# development_board.net
KiCad netlist of a schematic drawn in EAGLE
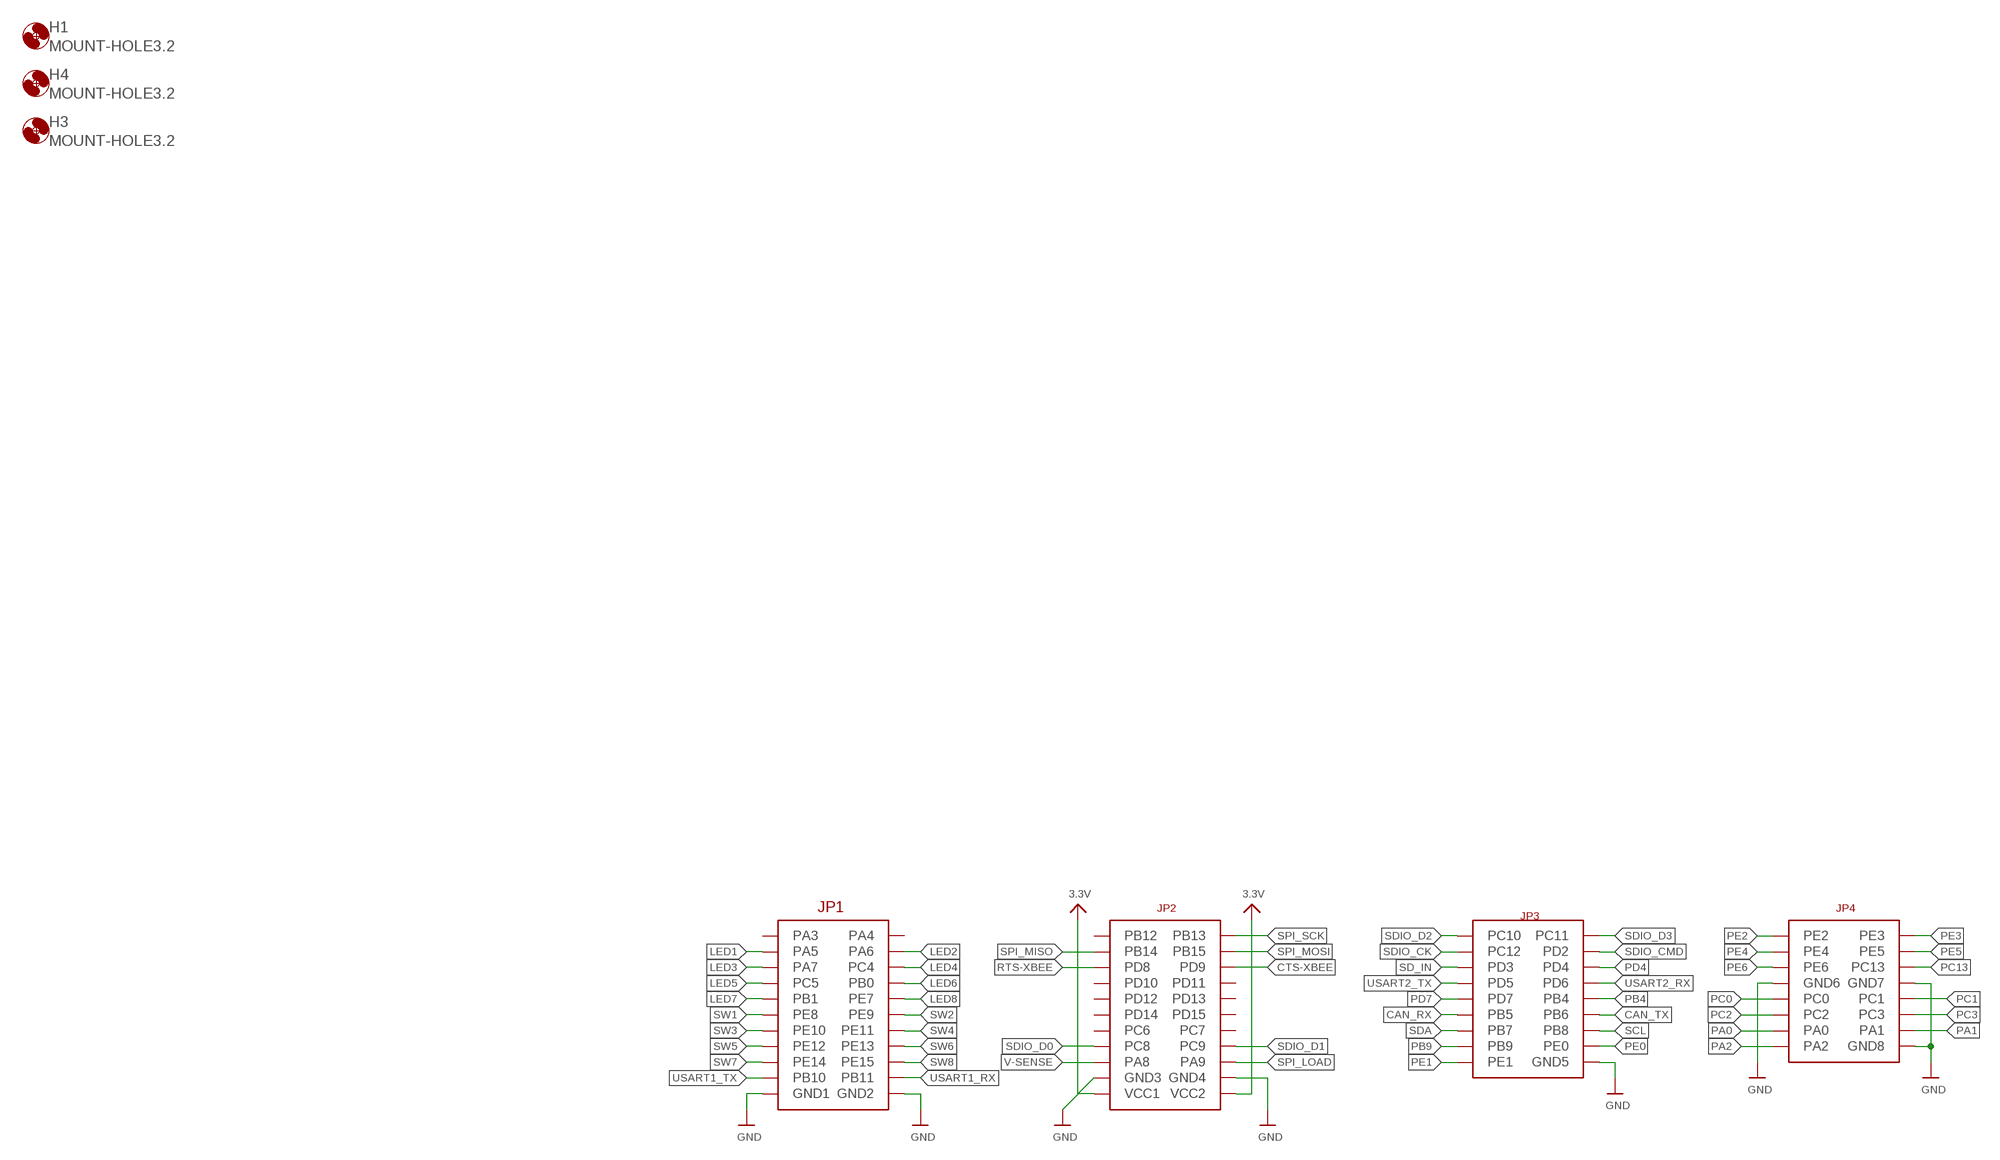
[diagram p0: schematic, sheet 1, part 1 of 3]
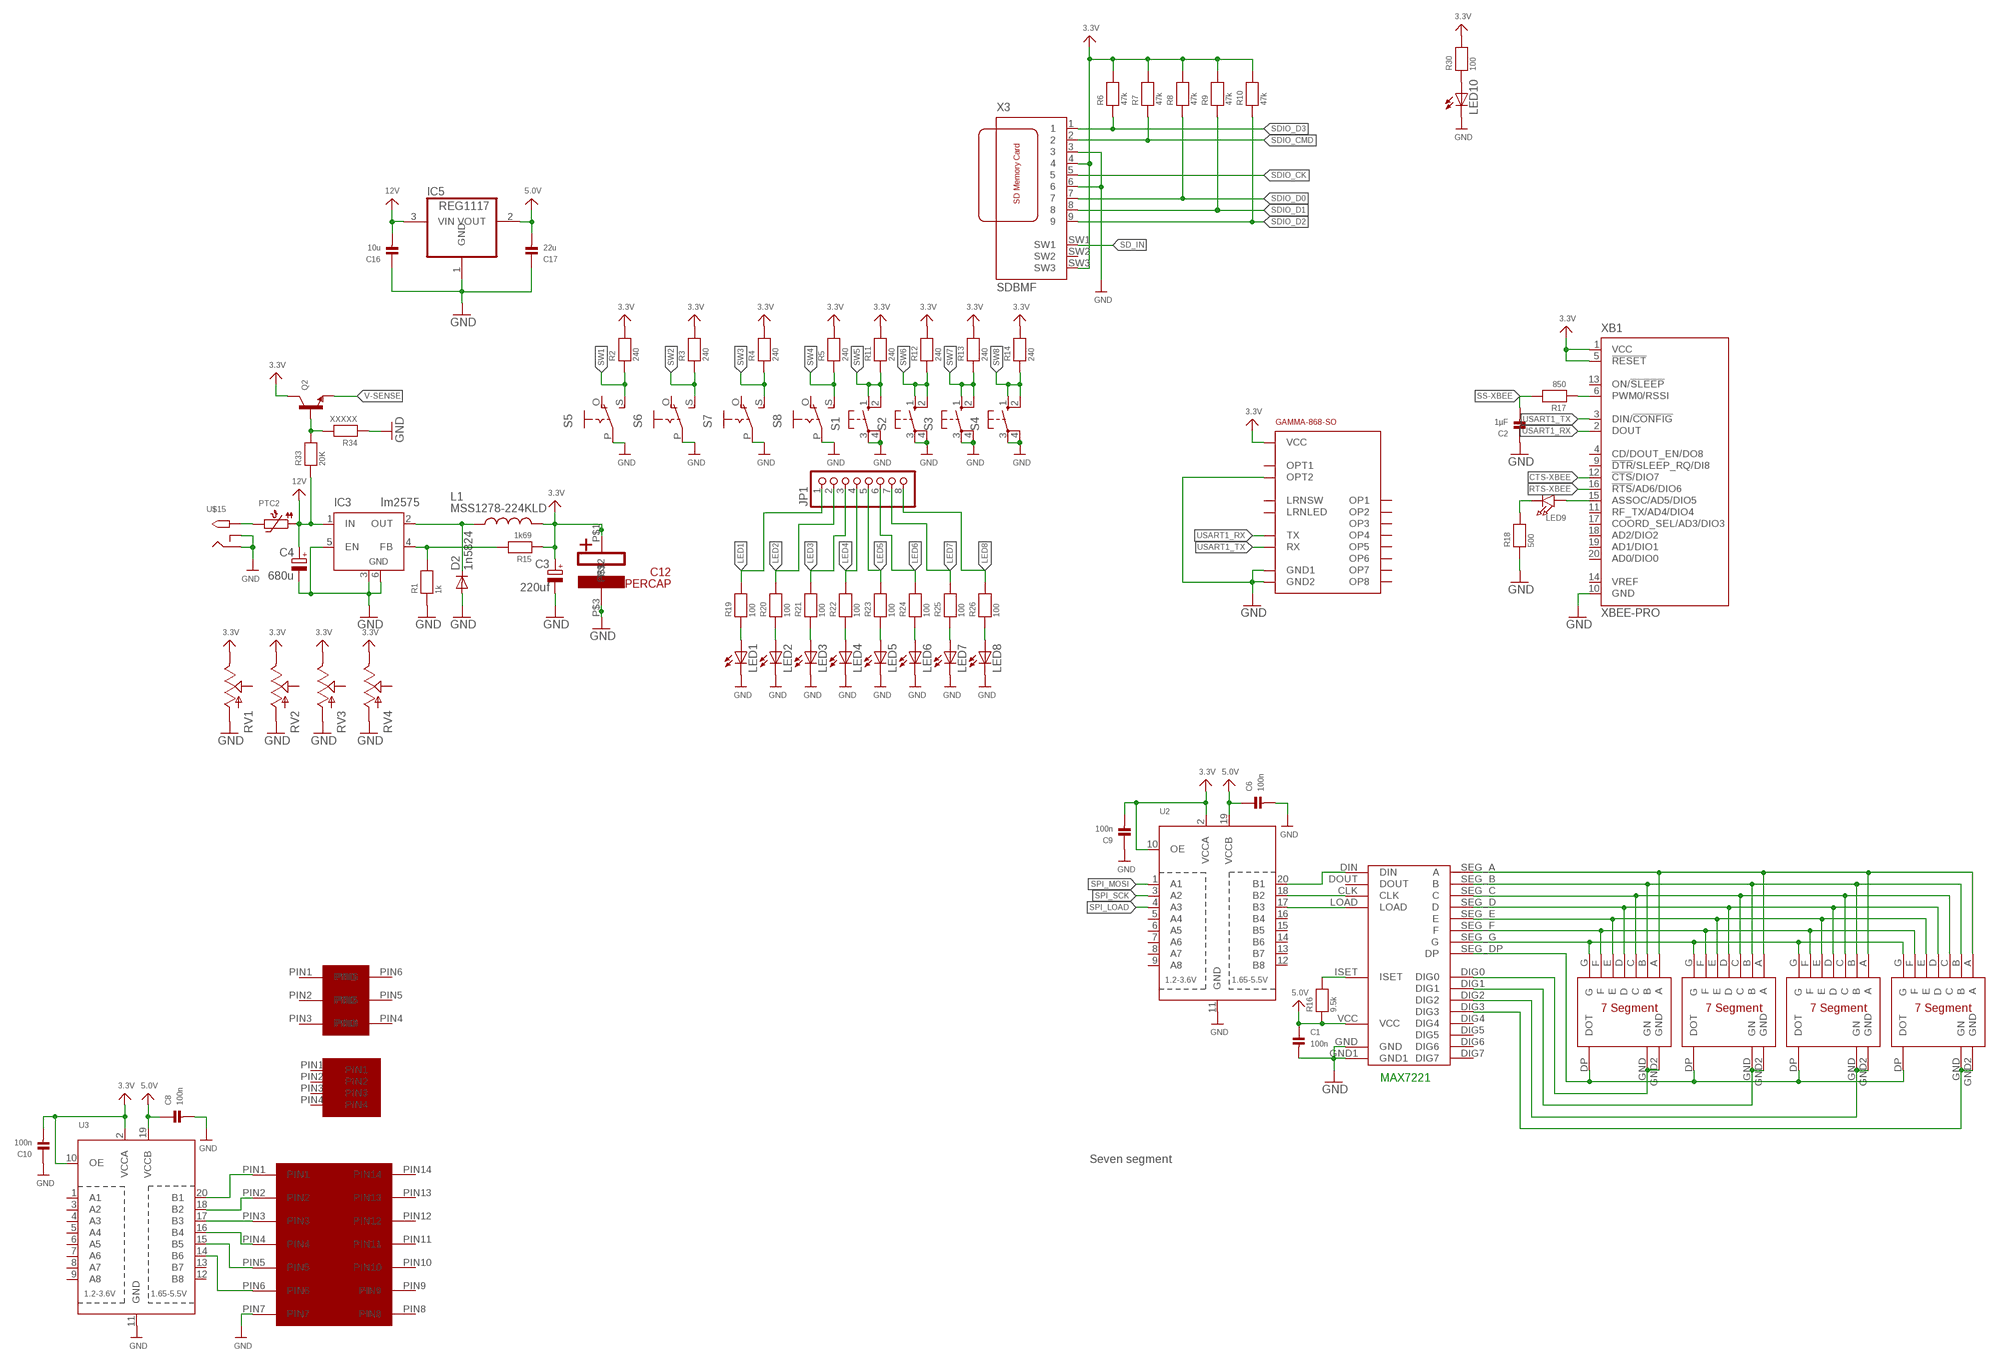
[diagram p1: schematic, sheet 1, part 2 of 3]
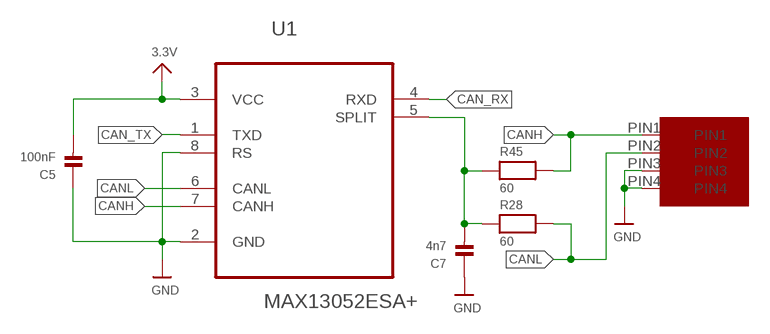
[diagram p2: schematic, sheet 1, part 3 of 3]

(export (version "E")
  (design (tool "Eeschema 10.0.6"))
  (components
    (comp (ref "C1")
      (value "100n")
      (footprint "eagle-import:_0603")
      (libsource (lib "eagle-import") (part "CAP_CERAMIC_0603"))
    )
    (comp (ref "C2")
      (value "1µF")
      (footprint "eagle-import:_0805")
      (libsource (lib "eagle-import") (part "CAP_CERAMIC_0805"))
    )
    (comp (ref "C3")
      (value "220uf")
      (footprint "eagle-import:E3,5-8")
      (libsource (lib "eagle-import") (part "CPOL-EUE3.5-8"))
    )
    (comp (ref "C4")
      (value "680u")
      (footprint "eagle-import:E5-10,5")
      (libsource (lib "eagle-import") (part "CPOL-EUE5-10.5"))
    )
    (comp (ref "C5")
      (value "100nF")
      (footprint "eagle-import:_0603")
      (libsource (lib "eagle-import") (part "CAP_CERAMIC_0603"))
    )
    (comp (ref "C6")
      (value "100n")
      (footprint "eagle-import:_0603")
      (libsource (lib "eagle-import") (part "CAP_CERAMIC_0603"))
    )
    (comp (ref "C7")
      (value "4n7")
      (footprint "eagle-import:_0603")
      (libsource (lib "eagle-import") (part "CAP_CERAMIC_0603"))
    )
    (comp (ref "C8")
      (value "100n")
      (footprint "eagle-import:_0603")
      (libsource (lib "eagle-import") (part "CAP_CERAMIC_0603"))
    )
    (comp (ref "C9")
      (value "100n")
      (footprint "eagle-import:_0603")
      (libsource (lib "eagle-import") (part "CAP_CERAMIC_0603"))
    )
    (comp (ref "C10")
      (value "100n")
      (footprint "eagle-import:_0603")
      (libsource (lib "eagle-import") (part "CAP_CERAMIC_0603"))
    )
    (comp (ref "C12")
      (value "SUPERCAP")
      (footprint "eagle-import:SUPERCAP")
      (libsource (lib "eagle-import") (part "SUPERCAP"))
    )
    (comp (ref "C16")
      (value "10u")
      (footprint "eagle-import:_0805")
      (libsource (lib "eagle-import") (part "CAP_CERAMIC_0805"))
    )
    (comp (ref "C17")
      (value "22u")
      (footprint "eagle-import:_0805")
      (libsource (lib "eagle-import") (part "CAP_CERAMIC_0805"))
    )
    (comp (ref "D2")
      (value "1n5824")
      (footprint "eagle-import:DO201-15")
      (libsource (lib "eagle-import") (part "1N5400"))
    )
    (comp (ref "H1")
      (value "MOUNT-HOLE3.2")
      (footprint "eagle-import:3,2")
      (libsource (lib "eagle-import") (part "MOUNT-HOLE3.2"))
    )
    (comp (ref "H3")
      (value "MOUNT-HOLE3.2")
      (footprint "eagle-import:3,2")
      (libsource (lib "eagle-import") (part "MOUNT-HOLE3.2"))
    )
    (comp (ref "H4")
      (value "MOUNT-HOLE3.2")
      (footprint "eagle-import:3,2")
      (libsource (lib "eagle-import") (part "MOUNT-HOLE3.2"))
    )
    (comp (ref "IC3")
      (value "lm2575")
      (footprint "eagle-import:TO263-5")
      (libsource (lib "eagle-import") (part "LM2596S"))
    )
    (comp (ref "IC5")
      (value "REG1117")
      (footprint "eagle-import:SOT223")
      (libsource (lib "eagle-import") (part "REG1117"))
    )
    (comp (ref "JP1")
      (value "PINHD-1X8BIG")
      (footprint "eagle-import:1X08-BIG")
      (libsource (lib "eagle-import") (part "PINHD-1X8BIG"))
    )
    (comp (ref "L1")
      (value "MSS1278-224KLD")
      (footprint "eagle-import:CDRH125")
      (libsource (lib "eagle-import") (part "INDUCTORPWR"))
    )
    (comp (ref "LED1")
      (value "LEDCHIPLED_1206")
      (footprint "eagle-import:CHIPLED_1206")
      (libsource (lib "eagle-import") (part "LEDCHIPLED_1206"))
    )
    (comp (ref "LED2")
      (value "LEDCHIPLED_1206")
      (footprint "eagle-import:CHIPLED_1206")
      (libsource (lib "eagle-import") (part "LEDCHIPLED_1206"))
    )
    (comp (ref "LED3")
      (value "LEDCHIPLED_1206")
      (footprint "eagle-import:CHIPLED_1206")
      (libsource (lib "eagle-import") (part "LEDCHIPLED_1206"))
    )
    (comp (ref "LED4")
      (value "LEDCHIPLED_1206")
      (footprint "eagle-import:CHIPLED_1206")
      (libsource (lib "eagle-import") (part "LEDCHIPLED_1206"))
    )
    (comp (ref "LED5")
      (value "LEDCHIPLED_1206")
      (footprint "eagle-import:CHIPLED_1206")
      (libsource (lib "eagle-import") (part "LEDCHIPLED_1206"))
    )
    (comp (ref "LED6")
      (value "LEDCHIPLED_1206")
      (footprint "eagle-import:CHIPLED_1206")
      (libsource (lib "eagle-import") (part "LEDCHIPLED_1206"))
    )
    (comp (ref "LED7")
      (value "LEDCHIPLED_1206")
      (footprint "eagle-import:CHIPLED_1206")
      (libsource (lib "eagle-import") (part "LEDCHIPLED_1206"))
    )
    (comp (ref "LED8")
      (value "LEDCHIPLED_1206")
      (footprint "eagle-import:CHIPLED_1206")
      (libsource (lib "eagle-import") (part "LEDCHIPLED_1206"))
    )
    (comp (ref "LED9")
      (value "LED1206")
      (footprint "eagle-import:CHIPLED_1206")
      (libsource (lib "eagle-import") (part "LED1206"))
    )
    (comp (ref "LED10")
      (value "LEDCHIPLED_1206")
      (footprint "eagle-import:CHIPLED_1206")
      (libsource (lib "eagle-import") (part "LEDCHIPLED_1206"))
    )
    (comp (ref "MAX7221")
      (value "MAX7221-SMD")
      (footprint "eagle-import:MAX7221")
      (libsource (lib "eagle-import") (part "MAX7221-SMD"))
    )
    (comp (ref "PTC2")
      (value "PTC1812")
      (footprint "eagle-import:PTC1812")
      (libsource (lib "eagle-import") (part "PTC1812"))
    )
    (comp (ref "Q2")
      (value "TRANSISTOR_NPNWIDE")
      (footprint "eagle-import:SOT23-WIDE")
      (libsource (lib "eagle-import") (part "TRANSISTOR_NPNWIDE"))
    )
    (comp (ref "R1")
      (value "1k")
      (footprint "eagle-import:_0603")
      (libsource (lib "eagle-import") (part "RESISTOR_0603"))
    )
    (comp (ref "R2")
      (value "240")
      (footprint "eagle-import:_0603")
      (libsource (lib "eagle-import") (part "RESISTOR_0603"))
    )
    (comp (ref "R3")
      (value "240")
      (footprint "eagle-import:_0603")
      (libsource (lib "eagle-import") (part "RESISTOR_0603"))
    )
    (comp (ref "R4")
      (value "240")
      (footprint "eagle-import:_0603")
      (libsource (lib "eagle-import") (part "RESISTOR_0603"))
    )
    (comp (ref "R5")
      (value "240")
      (footprint "eagle-import:_0603")
      (libsource (lib "eagle-import") (part "RESISTOR_0603"))
    )
    (comp (ref "R6")
      (value "47k")
      (footprint "eagle-import:_0603")
      (libsource (lib "eagle-import") (part "RESISTOR_0603"))
    )
    (comp (ref "R7")
      (value "47k")
      (footprint "eagle-import:_0603")
      (libsource (lib "eagle-import") (part "RESISTOR_0603"))
    )
    (comp (ref "R8")
      (value "47k")
      (footprint "eagle-import:_0603")
      (libsource (lib "eagle-import") (part "RESISTOR_0603"))
    )
    (comp (ref "R9")
      (value "47k")
      (footprint "eagle-import:_0603")
      (libsource (lib "eagle-import") (part "RESISTOR_0603"))
    )
    (comp (ref "R10")
      (value "47k")
      (footprint "eagle-import:_0603")
      (libsource (lib "eagle-import") (part "RESISTOR_0603"))
    )
    (comp (ref "R11")
      (value "240")
      (footprint "eagle-import:_0603")
      (libsource (lib "eagle-import") (part "RESISTOR_0603"))
    )
    (comp (ref "R12")
      (value "240")
      (footprint "eagle-import:_0603")
      (libsource (lib "eagle-import") (part "RESISTOR_0603"))
    )
    (comp (ref "R13")
      (value "240")
      (footprint "eagle-import:_0603")
      (libsource (lib "eagle-import") (part "RESISTOR_0603"))
    )
    (comp (ref "R14")
      (value "240")
      (footprint "eagle-import:_0603")
      (libsource (lib "eagle-import") (part "RESISTOR_0603"))
    )
    (comp (ref "R15")
      (value "1k69")
      (footprint "eagle-import:_0603")
      (libsource (lib "eagle-import") (part "RESISTOR_0603"))
    )
    (comp (ref "R16")
      (value "9.5k")
      (footprint "eagle-import:_0603")
      (libsource (lib "eagle-import") (part "RESISTOR_0603"))
    )
    (comp (ref "R17")
      (value "850")
      (footprint "eagle-import:_0603")
      (libsource (lib "eagle-import") (part "RESISTOR_0603"))
    )
    (comp (ref "R18")
      (value "500")
      (footprint "eagle-import:_0603")
      (libsource (lib "eagle-import") (part "RESISTOR_0603"))
    )
    (comp (ref "R19")
      (value "100")
      (footprint "eagle-import:_0603")
      (libsource (lib "eagle-import") (part "RESISTOR_0603"))
    )
    (comp (ref "R20")
      (value "100")
      (footprint "eagle-import:_0603")
      (libsource (lib "eagle-import") (part "RESISTOR_0603"))
    )
    (comp (ref "R21")
      (value "100")
      (footprint "eagle-import:_0603")
      (libsource (lib "eagle-import") (part "RESISTOR_0603"))
    )
    (comp (ref "R22")
      (value "100")
      (footprint "eagle-import:_0603")
      (libsource (lib "eagle-import") (part "RESISTOR_0603"))
    )
    (comp (ref "R23")
      (value "100")
      (footprint "eagle-import:_0603")
      (libsource (lib "eagle-import") (part "RESISTOR_0603"))
    )
    (comp (ref "R24")
      (value "100")
      (footprint "eagle-import:_0603")
      (libsource (lib "eagle-import") (part "RESISTOR_0603"))
    )
    (comp (ref "R25")
      (value "100")
      (footprint "eagle-import:_0603")
      (libsource (lib "eagle-import") (part "RESISTOR_0603"))
    )
    (comp (ref "R26")
      (value "100")
      (footprint "eagle-import:_0603")
      (libsource (lib "eagle-import") (part "RESISTOR_0603"))
    )
    (comp (ref "R28")
      (value "60")
      (footprint "eagle-import:_0603")
      (libsource (lib "eagle-import") (part "RESISTOR_0603"))
    )
    (comp (ref "R30")
      (value "100")
      (footprint "eagle-import:_0603")
      (libsource (lib "eagle-import") (part "RESISTOR_0603"))
    )
    (comp (ref "R33")
      (value "20K")
      (footprint "eagle-import:_0603")
      (libsource (lib "eagle-import") (part "RESISTOR_0603"))
    )
    (comp (ref "R34")
      (value "XXXXX")
      (footprint "eagle-import:_0603")
      (libsource (lib "eagle-import") (part "RESISTOR_0603"))
    )
    (comp (ref "R45")
      (value "60")
      (footprint "eagle-import:_0603")
      (libsource (lib "eagle-import") (part "RESISTOR_0603"))
    )
    (comp (ref "RV1")
      (value "POT")
      (footprint "eagle-import:ALPS_POT")
      (libsource (lib "eagle-import") (part "POT"))
    )
    (comp (ref "RV2")
      (value "POT")
      (footprint "eagle-import:ALPS_POT")
      (libsource (lib "eagle-import") (part "POT"))
    )
    (comp (ref "RV3")
      (value "POT")
      (footprint "eagle-import:ALPS_POT")
      (libsource (lib "eagle-import") (part "POT"))
    )
    (comp (ref "RV4")
      (value "POT")
      (footprint "eagle-import:ALPS_POT")
      (libsource (lib "eagle-import") (part "POT"))
    )
    (comp (ref "S1")
      (value "10-XX")
      (footprint "eagle-import:B3F-10XX")
      (fields
        (field (name "MPN") "B3F-1000")
        (field (name "MPN_1") "B3F-1000")
        (field (name "OC_FARNELL") "176432")
        (field (name "OC_NEWARK") "36M3542")
      )
      (libsource (lib "eagle-import") (part "10-XX"))
    )
    (comp (ref "S2")
      (value "10-XX")
      (footprint "eagle-import:B3F-10XX")
      (fields
        (field (name "MPN") "B3F-1000")
        (field (name "MPN_1") "B3F-1000")
        (field (name "OC_FARNELL") "176432")
        (field (name "OC_NEWARK") "36M3542")
      )
      (libsource (lib "eagle-import") (part "10-XX"))
    )
    (comp (ref "S3")
      (value "10-XX")
      (footprint "eagle-import:B3F-10XX")
      (fields
        (field (name "MPN") "B3F-1000")
        (field (name "MPN_1") "B3F-1000")
        (field (name "OC_FARNELL") "176432")
        (field (name "OC_NEWARK") "36M3542")
      )
      (libsource (lib "eagle-import") (part "10-XX"))
    )
    (comp (ref "S4")
      (value "10-XX")
      (footprint "eagle-import:B3F-10XX")
      (fields
        (field (name "MPN") "B3F-1000")
        (field (name "MPN_1") "B3F-1000")
        (field (name "OC_FARNELL") "176432")
        (field (name "OC_NEWARK") "36M3542")
      )
      (libsource (lib "eagle-import") (part "10-XX"))
    )
    (comp (ref "S5")
      (value "EG1218S")
      (footprint "eagle-import:EG1218")
      (libsource (lib "eagle-import") (part "EG1218S"))
    )
    (comp (ref "S6")
      (value "EG1218S")
      (footprint "eagle-import:EG1218")
      (libsource (lib "eagle-import") (part "EG1218S"))
    )
    (comp (ref "S7")
      (value "EG1218S")
      (footprint "eagle-import:EG1218")
      (libsource (lib "eagle-import") (part "EG1218S"))
    )
    (comp (ref "S8")
      (value "EG1218S")
      (footprint "eagle-import:EG1218")
      (libsource (lib "eagle-import") (part "EG1218S"))
    )
    (comp (ref "U$1")
      (value "CPU-BOARD")
      (footprint "eagle-import:CPU-BOARD-JP1")
      (libsource (lib "eagle-import") (part "CPU-BOARD"))
    )
    (comp (ref "U$2")
      (value "GAMMA-868-SO")
      (footprint "eagle-import:UNICORN_V2_GAMMA-868-SO")
      (libsource (lib "eagle-import") (part "GAMMA-868-SO"))
    )
    (comp (ref "U$15")
      (value "2.1MMJACKSMT")
      (footprint "eagle-import:DCJACK_2MM_SMT")
      (libsource (lib "eagle-import") (part "2.1MMJACKSMT"))
    )
    (comp (ref "U$23")
      (value "REDSEVENSEGMENT")
      (footprint "eagle-import:REDSEGMENT")
      (libsource (lib "eagle-import") (part "REDSEVENSEGMENT"))
    )
    (comp (ref "U$24")
      (value "REDSEVENSEGMENT")
      (footprint "eagle-import:REDSEGMENT")
      (libsource (lib "eagle-import") (part "REDSEVENSEGMENT"))
    )
    (comp (ref "U$25")
      (value "REDSEVENSEGMENT")
      (footprint "eagle-import:REDSEGMENT")
      (libsource (lib "eagle-import") (part "REDSEVENSEGMENT"))
    )
    (comp (ref "U$26")
      (value "REDSEVENSEGMENT")
      (footprint "eagle-import:REDSEGMENT")
      (libsource (lib "eagle-import") (part "REDSEVENSEGMENT"))
    )
    (comp (ref "U$57")
      (value "MICROFIT4")
      (footprint "eagle-import:MICROFIT4SOCK")
      (libsource (lib "eagle-import") (part "MICROFIT4"))
    )
    (comp (ref "U$61")
      (value "MICROFIT14")
      (footprint "eagle-import:MICROFIT14SOCK")
      (libsource (lib "eagle-import") (part "MICROFIT14"))
    )
    (comp (ref "U$67")
      (value "MICROFIT4")
      (footprint "eagle-import:MICROFIT4SOCK")
      (libsource (lib "eagle-import") (part "MICROFIT4"))
    )
    (comp (ref "U$68")
      (value "MICROFIT6")
      (footprint "eagle-import:MICROFIT6SOCK")
      (libsource (lib "eagle-import") (part "MICROFIT6"))
    )
    (comp (ref "U1")
      (value "MAX13052ESA+")
      (footprint "eagle-import:SOIC127P600X175-8N")
      (libsource (lib "eagle-import") (part "MAX13052ESA+"))
    )
    (comp (ref "U2")
      (value "TXB0108PWR")
      (footprint "eagle-import:TSSOP20")
      (libsource (lib "eagle-import") (part "TXB0108PWR"))
    )
    (comp (ref "U3")
      (value "TXB0108PWR")
      (footprint "eagle-import:TSSOP20")
      (libsource (lib "eagle-import") (part "TXB0108PWR"))
    )
    (comp (ref "X3")
      (value "SDBMF")
      (footprint "eagle-import:SDBMF-009XXBXX2")
      (libsource (lib "eagle-import") (part "SDBMF"))
    )
    (comp (ref "XB1")
      (value "XBEE-PRO")
      (footprint "eagle-import:XBEE-PRO")
      (fields (field (name "MPN") "XBP24-AWI-001"))
      (libsource (lib "eagle-import") (part "XBEE-PRO"))
    )
  )
  (nets
    (net (code "1") (name "3.3V") (class "Default")
      (node (ref "C10") (pin "2") (pinfunction "P$2_2") (pintype "passive"))
      (node (ref "C12") (pin "P$1") (pinfunction "P$1_P$1") (pintype "bidirectional"))
      (node (ref "C3") (pin "+") (pinfunction "+_+") (pintype "passive"))
      (node (ref "C5") (pin "2") (pinfunction "P$2_2") (pintype "passive"))
      (node (ref "C9") (pin "2") (pinfunction "P$2_2") (pintype "passive"))
      (node (ref "L1") (pin "2") (pinfunction "2_2") (pintype "passive"))
      (node (ref "Q2") (pin "3") (pinfunction "C_3") (pintype "passive"))
      (node (ref "R10") (pin "2") (pinfunction "2_2") (pintype "passive"))
      (node (ref "R11") (pin "2") (pinfunction "2_2") (pintype "passive"))
      (node (ref "R12") (pin "2") (pinfunction "2_2") (pintype "passive"))
      (node (ref "R13") (pin "2") (pinfunction "2_2") (pintype "passive"))
      (node (ref "R14") (pin "2") (pinfunction "2_2") (pintype "passive"))
      (node (ref "R15") (pin "1") (pinfunction "1_1") (pintype "passive"))
      (node (ref "R2") (pin "2") (pinfunction "2_2") (pintype "passive"))
      (node (ref "R3") (pin "2") (pinfunction "2_2") (pintype "passive"))
      (node (ref "R30") (pin "2") (pinfunction "2_2") (pintype "passive"))
      (node (ref "R4") (pin "2") (pinfunction "2_2") (pintype "passive"))
      (node (ref "R5") (pin "2") (pinfunction "2_2") (pintype "passive"))
      (node (ref "R6") (pin "2") (pinfunction "2_2") (pintype "passive"))
      (node (ref "R7") (pin "2") (pinfunction "2_2") (pintype "passive"))
      (node (ref "R8") (pin "2") (pinfunction "2_2") (pintype "passive"))
      (node (ref "R9") (pin "2") (pinfunction "2_2") (pintype "passive"))
      (node (ref "RV1") (pin "P$1") (pinfunction "E_P$1") (pintype "passive"))
      (node (ref "RV2") (pin "P$1") (pinfunction "E_P$1") (pintype "passive"))
      (node (ref "RV3") (pin "P$1") (pinfunction "E_P$1") (pintype "passive"))
      (node (ref "RV4") (pin "P$1") (pinfunction "E_P$1") (pintype "passive"))
      (node (ref "U$1") (pin "P$43") (pinfunction "VCC1_P$43") (pintype "bidirectional"))
      (node (ref "U$1") (pin "P$44") (pinfunction "VCC2_P$44") (pintype "bidirectional"))
      (node (ref "U$2") (pin "P$16") (pinfunction "VCC_P$16") (pintype "bidirectional"))
      (node (ref "U1") (pin "3") (pinfunction "VCC_3") (pintype "power_in"))
      (node (ref "U2") (pin "10") (pinfunction "OE_10") (pintype "bidirectional"))
      (node (ref "U2") (pin "2") (pinfunction "VCCA_2") (pintype "bidirectional"))
      (node (ref "U3") (pin "10") (pinfunction "OE_10") (pintype "bidirectional"))
      (node (ref "U3") (pin "2") (pinfunction "VCCA_2") (pintype "bidirectional"))
      (node (ref "X3") (pin "4") (pinfunction "4_4") (pintype "passive"))
      (node (ref "X3") (pin "SW3") (pinfunction "SW3_SW3") (pintype "passive"))
      (node (ref "XB1") (pin "1") (pinfunction "VCC_1") (pintype "power_in"))
      (node (ref "XB1") (pin "5") (pinfunction "~{RESET}_5") (pintype "input"))
    )
    (net (code "2") (name "5.0V") (class "Default")
      (node (ref "C1") (pin "1") (pinfunction "P$1_1") (pintype "passive"))
      (node (ref "C17") (pin "2") (pinfunction "P$2_2") (pintype "passive"))
      (node (ref "C6") (pin "1") (pinfunction "P$1_1") (pintype "passive"))
      (node (ref "C8") (pin "1") (pinfunction "P$1_1") (pintype "passive"))
      (node (ref "IC5") (pin "2") (pinfunction "VOUT_2") (pintype "output"))
      (node (ref "MAX7221") (pin "VCC") (pinfunction "VCC_VCC") (pintype "bidirectional"))
      (node (ref "R16") (pin "1") (pinfunction "1_1") (pintype "passive"))
      (node (ref "U2") (pin "19") (pinfunction "VCCB_19") (pintype "bidirectional"))
      (node (ref "U3") (pin "19") (pinfunction "VCCB_19") (pintype "bidirectional"))
    )
    (net (code "3") (name "12V") (class "Default")
      (node (ref "C16") (pin "2") (pinfunction "P$2_2") (pintype "passive"))
      (node (ref "C4") (pin "+") (pinfunction "+_+") (pintype "passive"))
      (node (ref "IC3") (pin "1") (pinfunction "IN_1") (pintype "input"))
      (node (ref "IC5") (pin "3") (pinfunction "VIN_3") (pintype "input"))
      (node (ref "PTC2") (pin "P$1") (pinfunction "1_P$1") (pintype "passive"))
      (node (ref "R33") (pin "1") (pinfunction "1_1") (pintype "passive"))
    )
    (net (code "4") (name "CANH") (class "Default")
      (node (ref "R45") (pin "2") (pinfunction "2_2") (pintype "passive"))
      (node (ref "U$57") (pin "PIN1") (pinfunction "PIN1_PIN1") (pintype "bidirectional"))
      (node (ref "U1") (pin "7") (pinfunction "CANH_7") (pintype "input"))
    )
    (net (code "5") (name "CANL") (class "Default")
      (node (ref "R28") (pin "2") (pinfunction "2_2") (pintype "passive"))
      (node (ref "U$57") (pin "PIN2") (pinfunction "PIN2_PIN2") (pintype "bidirectional"))
      (node (ref "U1") (pin "6") (pinfunction "CANL_6") (pintype "input"))
    )
    (net (code "6") (name "CAN_RX") (class "Default")
      (node (ref "U$1") (pin "P$55") (pinfunction "PB5_P$55") (pintype "bidirectional"))
      (node (ref "U1") (pin "4") (pinfunction "RXD_4") (pintype "output"))
    )
    (net (code "7") (name "CAN_TX") (class "Default")
      (node (ref "U$1") (pin "P$56") (pinfunction "PB6_P$56") (pintype "bidirectional"))
      (node (ref "U1") (pin "1") (pinfunction "TXD_1") (pintype "input"))
    )
    (net (code "8") (name "CTS-XBEE") (class "Default")
      (node (ref "U$1") (pin "P$28") (pinfunction "PD9_P$28") (pintype "bidirectional"))
      (node (ref "XB1") (pin "12") (pinfunction "~{CTS}/DIO7_12") (pintype "bidirectional"))
    )
    (net (code "9") (name "GND") (class "Default")
      (node (ref "C1") (pin "2") (pinfunction "P$2_2") (pintype "passive"))
      (node (ref "C10") (pin "1") (pinfunction "P$1_1") (pintype "passive"))
      (node (ref "C12") (pin "P$3") (pinfunction "P$2_P$3") (pintype "bidirectional"))
      (node (ref "C16") (pin "1") (pinfunction "P$1_1") (pintype "passive"))
      (node (ref "C17") (pin "1") (pinfunction "P$1_1") (pintype "passive"))
      (node (ref "C2") (pin "1") (pinfunction "P$1_1") (pintype "passive"))
      (node (ref "C3") (pin "-") (pinfunction "-_-") (pintype "passive"))
      (node (ref "C4") (pin "-") (pinfunction "-_-") (pintype "passive"))
      (node (ref "C5") (pin "1") (pinfunction "P$1_1") (pintype "passive"))
      (node (ref "C6") (pin "2") (pinfunction "P$2_2") (pintype "passive"))
      (node (ref "C7") (pin "1") (pinfunction "P$1_1") (pintype "passive"))
      (node (ref "C8") (pin "2") (pinfunction "P$2_2") (pintype "passive"))
      (node (ref "C9") (pin "1") (pinfunction "P$1_1") (pintype "passive"))
      (node (ref "D2") (pin "A") (pinfunction "A_A") (pintype "passive"))
      (node (ref "IC3") (pin "3") (pinfunction "GND_3") (pintype "power_in"))
      (node (ref "IC3") (pin "5") (pinfunction "EN_5") (pintype "input"))
      (node (ref "IC3") (pin "6") (pinfunction "GND_6") (pintype "power_in"))
      (node (ref "IC5") (pin "1") (pinfunction "GND_1") (pintype "power_in"))
      (node (ref "LED1") (pin "C") (pinfunction "C_C") (pintype "passive"))
      (node (ref "LED10") (pin "C") (pinfunction "C_C") (pintype "passive"))
      (node (ref "LED2") (pin "C") (pinfunction "C_C") (pintype "passive"))
      (node (ref "LED3") (pin "C") (pinfunction "C_C") (pintype "passive"))
      (node (ref "LED4") (pin "C") (pinfunction "C_C") (pintype "passive"))
      (node (ref "LED5") (pin "C") (pinfunction "C_C") (pintype "passive"))
      (node (ref "LED6") (pin "C") (pinfunction "C_C") (pintype "passive"))
      (node (ref "LED7") (pin "C") (pinfunction "C_C") (pintype "passive"))
      (node (ref "LED8") (pin "C") (pinfunction "C_C") (pintype "passive"))
      (node (ref "MAX7221") (pin "GND") (pinfunction "GND_GND") (pintype "bidirectional"))
      (node (ref "MAX7221") (pin "GND1") (pinfunction "GND1_GND1") (pintype "bidirectional"))
      (node (ref "R1") (pin "1") (pinfunction "1_1") (pintype "passive"))
      (node (ref "R18") (pin "1") (pinfunction "1_1") (pintype "passive"))
      (node (ref "R34") (pin "1") (pinfunction "1_1") (pintype "passive"))
      (node (ref "RV1") (pin "P$3") (pinfunction "A_P$3") (pintype "passive"))
      (node (ref "RV2") (pin "P$3") (pinfunction "A_P$3") (pintype "passive"))
      (node (ref "RV3") (pin "P$3") (pinfunction "A_P$3") (pintype "passive"))
      (node (ref "RV4") (pin "P$3") (pinfunction "A_P$3") (pintype "passive"))
      (node (ref "S1") (pin "3") (pinfunction "P_3") (pintype "passive"))
      (node (ref "S1") (pin "4") (pinfunction "P1_4") (pintype "passive"))
      (node (ref "S2") (pin "3") (pinfunction "P_3") (pintype "passive"))
      (node (ref "S2") (pin "4") (pinfunction "P1_4") (pintype "passive"))
      (node (ref "S3") (pin "3") (pinfunction "P_3") (pintype "passive"))
      (node (ref "S3") (pin "4") (pinfunction "P1_4") (pintype "passive"))
      (node (ref "S4") (pin "3") (pinfunction "P_3") (pintype "passive"))
      (node (ref "S4") (pin "4") (pinfunction "P1_4") (pintype "passive"))
      (node (ref "S5") (pin "P") (pinfunction "P_P") (pintype "passive"))
      (node (ref "S6") (pin "P") (pinfunction "P_P") (pintype "passive"))
      (node (ref "S7") (pin "P") (pinfunction "P_P") (pintype "passive"))
      (node (ref "S8") (pin "P") (pinfunction "P_P") (pintype "passive"))
      (node (ref "U$1") (pin "P$19") (pinfunction "GND1_P$19") (pintype "bidirectional"))
      (node (ref "U$1") (pin "P$20") (pinfunction "GND2_P$20") (pintype "bidirectional"))
      (node (ref "U$1") (pin "P$41") (pinfunction "GND3_P$41") (pintype "bidirectional"))
      (node (ref "U$1") (pin "P$42") (pinfunction "GND4_P$42") (pintype "bidirectional"))
      (node (ref "U$1") (pin "P$62") (pinfunction "GND5_P$62") (pintype "bidirectional"))
      (node (ref "U$1") (pin "P$69") (pinfunction "GND6_P$69") (pintype "bidirectional"))
      (node (ref "U$1") (pin "P$70") (pinfunction "GND7_P$70") (pintype "bidirectional"))
      (node (ref "U$1") (pin "P$78") (pinfunction "GND8_P$78") (pintype "bidirectional"))
      (node (ref "U$15") (pin "GND") (pinfunction "RING_GND") (pintype "bidirectional"))
      (node (ref "U$15") (pin "GNDBREAK") (pinfunction "RING_SW_GNDBREAK") (pintype "bidirectional"))
      (node (ref "U$2") (pin "P$14") (pinfunction "OPT2_P$14") (pintype "bidirectional"))
      (node (ref "U$2") (pin "P$15") (pinfunction "GND2_P$15") (pintype "bidirectional"))
      (node (ref "U$2") (pin "P$2") (pinfunction "GND1_P$2") (pintype "bidirectional"))
      (node (ref "U$57") (pin "PIN3") (pinfunction "PIN3_PIN3") (pintype "bidirectional"))
      (node (ref "U$57") (pin "PIN4") (pinfunction "PIN4_PIN4") (pintype "bidirectional"))
      (node (ref "U$61") (pin "PIN7") (pinfunction "PIN7_PIN7") (pintype "bidirectional"))
      (node (ref "U1") (pin "2") (pinfunction "GND_2") (pintype "passive"))
      (node (ref "U1") (pin "8") (pinfunction "RS_8") (pintype "input"))
      (node (ref "U2") (pin "11") (pinfunction "GND_11") (pintype "bidirectional"))
      (node (ref "U3") (pin "11") (pinfunction "GND_11") (pintype "bidirectional"))
      (node (ref "X3") (pin "3") (pinfunction "3_3") (pintype "passive"))
      (node (ref "X3") (pin "6") (pinfunction "6_6") (pintype "passive"))
      (node (ref "XB1") (pin "10") (pinfunction "GND_10") (pintype "power_in"))
    )
    (net (code "10") (name "LED1") (class "Default")
      (node (ref "JP1") (pin "1") (pinfunction "1_1") (pintype "passive"))
      (node (ref "R19") (pin "2") (pinfunction "2_2") (pintype "passive"))
      (node (ref "U$1") (pin "P$3") (pinfunction "PA5_P$3") (pintype "bidirectional"))
    )
    (net (code "11") (name "LED2") (class "Default")
      (node (ref "JP1") (pin "2") (pinfunction "2_2") (pintype "passive"))
      (node (ref "R20") (pin "2") (pinfunction "2_2") (pintype "passive"))
      (node (ref "U$1") (pin "P$4") (pinfunction "PA6_P$4") (pintype "bidirectional"))
    )
    (net (code "12") (name "LED3") (class "Default")
      (node (ref "JP1") (pin "3") (pinfunction "3_3") (pintype "passive"))
      (node (ref "R21") (pin "2") (pinfunction "2_2") (pintype "passive"))
      (node (ref "U$1") (pin "P$5") (pinfunction "PA7_P$5") (pintype "bidirectional"))
    )
    (net (code "13") (name "LED4") (class "Default")
      (node (ref "JP1") (pin "4") (pinfunction "4_4") (pintype "passive"))
      (node (ref "R22") (pin "2") (pinfunction "2_2") (pintype "passive"))
      (node (ref "U$1") (pin "P$6") (pinfunction "PC4_P$6") (pintype "bidirectional"))
    )
    (net (code "14") (name "LED5") (class "Default")
      (node (ref "JP1") (pin "5") (pinfunction "5_5") (pintype "passive"))
      (node (ref "R23") (pin "2") (pinfunction "2_2") (pintype "passive"))
      (node (ref "U$1") (pin "P$7") (pinfunction "PC5_P$7") (pintype "bidirectional"))
    )
    (net (code "15") (name "LED6") (class "Default")
      (node (ref "JP1") (pin "6") (pinfunction "6_6") (pintype "passive"))
      (node (ref "R24") (pin "2") (pinfunction "2_2") (pintype "passive"))
      (node (ref "U$1") (pin "P$8") (pinfunction "PB0_P$8") (pintype "bidirectional"))
    )
    (net (code "16") (name "LED7") (class "Default")
      (node (ref "JP1") (pin "7") (pinfunction "7_7") (pintype "passive"))
      (node (ref "R25") (pin "2") (pinfunction "2_2") (pintype "passive"))
      (node (ref "U$1") (pin "P$9") (pinfunction "PB1_P$9") (pintype "bidirectional"))
    )
    (net (code "17") (name "LED8") (class "Default")
      (node (ref "JP1") (pin "8") (pinfunction "8_8") (pintype "passive"))
      (node (ref "R26") (pin "2") (pinfunction "2_2") (pintype "passive"))
      (node (ref "U$1") (pin "P$10") (pinfunction "PE7_P$10") (pintype "bidirectional"))
    )
    (net (code "18") (name "Net-(C7-P$2)") (class "Default")
      (node (ref "C7") (pin "2") (pinfunction "P$2_2") (pintype "passive"))
      (node (ref "R28") (pin "1") (pinfunction "1_1") (pintype "passive"))
      (node (ref "R45") (pin "1") (pinfunction "1_1") (pintype "passive"))
      (node (ref "U1") (pin "5") (pinfunction "SPLIT_5") (pintype "output"))
    )
    (net (code "19") (name "Net-(IC3-FB)") (class "Default")
      (node (ref "IC3") (pin "4") (pinfunction "FB_4") (pintype "input"))
      (node (ref "R1") (pin "2") (pinfunction "2_2") (pintype "passive"))
      (node (ref "R15") (pin "2") (pinfunction "2_2") (pintype "passive"))
    )
    (net (code "20") (name "Net-(IC3-OUT)") (class "Default")
      (node (ref "D2") (pin "C") (pinfunction "C_C") (pintype "passive"))
      (node (ref "IC3") (pin "2") (pinfunction "OUT_2") (pintype "output"))
      (node (ref "L1") (pin "1") (pinfunction "1_1") (pintype "passive"))
    )
    (net (code "21") (name "Net-(LED1-PadA)") (class "Default")
      (node (ref "LED1") (pin "A") (pinfunction "A_A") (pintype "passive"))
      (node (ref "R19") (pin "1") (pinfunction "1_1") (pintype "passive"))
    )
    (net (code "22") (name "Net-(LED2-PadA)") (class "Default")
      (node (ref "LED2") (pin "A") (pinfunction "A_A") (pintype "passive"))
      (node (ref "R20") (pin "1") (pinfunction "1_1") (pintype "passive"))
    )
    (net (code "23") (name "Net-(LED3-PadA)") (class "Default")
      (node (ref "LED3") (pin "A") (pinfunction "A_A") (pintype "passive"))
      (node (ref "R21") (pin "1") (pinfunction "1_1") (pintype "passive"))
    )
    (net (code "24") (name "Net-(LED4-PadA)") (class "Default")
      (node (ref "LED4") (pin "A") (pinfunction "A_A") (pintype "passive"))
      (node (ref "R22") (pin "1") (pinfunction "1_1") (pintype "passive"))
    )
    (net (code "25") (name "Net-(LED5-PadA)") (class "Default")
      (node (ref "LED5") (pin "A") (pinfunction "A_A") (pintype "passive"))
      (node (ref "R23") (pin "1") (pinfunction "1_1") (pintype "passive"))
    )
    (net (code "26") (name "Net-(LED6-PadA)") (class "Default")
      (node (ref "LED6") (pin "A") (pinfunction "A_A") (pintype "passive"))
      (node (ref "R24") (pin "1") (pinfunction "1_1") (pintype "passive"))
    )
    (net (code "27") (name "Net-(LED7-PadA)") (class "Default")
      (node (ref "LED7") (pin "A") (pinfunction "A_A") (pintype "passive"))
      (node (ref "R25") (pin "1") (pinfunction "1_1") (pintype "passive"))
    )
    (net (code "28") (name "Net-(LED8-PadA)") (class "Default")
      (node (ref "LED8") (pin "A") (pinfunction "A_A") (pintype "passive"))
      (node (ref "R26") (pin "1") (pinfunction "1_1") (pintype "passive"))
    )
    (net (code "29") (name "Net-(LED9-PadC)") (class "Default")
      (node (ref "LED9") (pin "C") (pinfunction "C_C") (pintype "passive"))
      (node (ref "R18") (pin "2") (pinfunction "2_2") (pintype "passive"))
    )
    (net (code "30") (name "Net-(LED10-PadA)") (class "Default")
      (node (ref "LED10") (pin "A") (pinfunction "A_A") (pintype "passive"))
      (node (ref "R30") (pin "1") (pinfunction "1_1") (pintype "passive"))
    )
    (net (code "31") (name "Net-(MAX7221-A)") (class "Default")
      (node (ref "MAX7221") (pin "SEG_A") (pinfunction "A_SEG_A") (pintype "bidirectional"))
      (node (ref "U$23") (pin "A") (pinfunction "A_A") (pintype "bidirectional"))
      (node (ref "U$24") (pin "A") (pinfunction "A_A") (pintype "bidirectional"))
      (node (ref "U$25") (pin "A") (pinfunction "A_A") (pintype "bidirectional"))
      (node (ref "U$26") (pin "A") (pinfunction "A_A") (pintype "bidirectional"))
    )
    (net (code "32") (name "Net-(MAX7221-B)") (class "Default")
      (node (ref "MAX7221") (pin "SEG_B") (pinfunction "B_SEG_B") (pintype "bidirectional"))
      (node (ref "U$23") (pin "B") (pinfunction "B_B") (pintype "bidirectional"))
      (node (ref "U$24") (pin "B") (pinfunction "B_B") (pintype "bidirectional"))
      (node (ref "U$25") (pin "B") (pinfunction "B_B") (pintype "bidirectional"))
      (node (ref "U$26") (pin "B") (pinfunction "B_B") (pintype "bidirectional"))
    )
    (net (code "33") (name "Net-(MAX7221-C)") (class "Default")
      (node (ref "MAX7221") (pin "SEG_C") (pinfunction "C_SEG_C") (pintype "bidirectional"))
      (node (ref "U$23") (pin "C") (pinfunction "C_C") (pintype "bidirectional"))
      (node (ref "U$24") (pin "C") (pinfunction "C_C") (pintype "bidirectional"))
      (node (ref "U$25") (pin "C") (pinfunction "C_C") (pintype "bidirectional"))
      (node (ref "U$26") (pin "C") (pinfunction "C_C") (pintype "bidirectional"))
    )
    (net (code "34") (name "Net-(MAX7221-D)") (class "Default")
      (node (ref "MAX7221") (pin "SEG_D") (pinfunction "D_SEG_D") (pintype "bidirectional"))
      (node (ref "U$23") (pin "D") (pinfunction "D_D") (pintype "bidirectional"))
      (node (ref "U$24") (pin "D") (pinfunction "D_D") (pintype "bidirectional"))
      (node (ref "U$25") (pin "D") (pinfunction "D_D") (pintype "bidirectional"))
      (node (ref "U$26") (pin "D") (pinfunction "D_D") (pintype "bidirectional"))
    )
    (net (code "35") (name "Net-(MAX7221-DP)") (class "Default")
      (node (ref "MAX7221") (pin "SEG_DP") (pinfunction "DP_SEG_DP") (pintype "bidirectional"))
      (node (ref "U$23") (pin "DP") (pinfunction "DOT_DP") (pintype "bidirectional"))
      (node (ref "U$24") (pin "DP") (pinfunction "DOT_DP") (pintype "bidirectional"))
      (node (ref "U$25") (pin "DP") (pinfunction "DOT_DP") (pintype "bidirectional"))
      (node (ref "U$26") (pin "DP") (pinfunction "DOT_DP") (pintype "bidirectional"))
    )
    (net (code "36") (name "Net-(MAX7221-E)") (class "Default")
      (node (ref "MAX7221") (pin "SEG_E") (pinfunction "E_SEG_E") (pintype "bidirectional"))
      (node (ref "U$23") (pin "E") (pinfunction "E_E") (pintype "bidirectional"))
      (node (ref "U$24") (pin "E") (pinfunction "E_E") (pintype "bidirectional"))
      (node (ref "U$25") (pin "E") (pinfunction "E_E") (pintype "bidirectional"))
      (node (ref "U$26") (pin "E") (pinfunction "E_E") (pintype "bidirectional"))
    )
    (net (code "37") (name "Net-(MAX7221-F)") (class "Default")
      (node (ref "MAX7221") (pin "SEG_F") (pinfunction "F_SEG_F") (pintype "bidirectional"))
      (node (ref "U$23") (pin "F") (pinfunction "F_F") (pintype "bidirectional"))
      (node (ref "U$24") (pin "F") (pinfunction "F_F") (pintype "bidirectional"))
      (node (ref "U$25") (pin "F") (pinfunction "F_F") (pintype "bidirectional"))
      (node (ref "U$26") (pin "F") (pinfunction "F_F") (pintype "bidirectional"))
    )
    (net (code "38") (name "Net-(MAX7221-G)") (class "Default")
      (node (ref "MAX7221") (pin "SEG_G") (pinfunction "G_SEG_G") (pintype "bidirectional"))
      (node (ref "U$23") (pin "G") (pinfunction "G_G") (pintype "bidirectional"))
      (node (ref "U$24") (pin "G") (pinfunction "G_G") (pintype "bidirectional"))
      (node (ref "U$25") (pin "G") (pinfunction "G_G") (pintype "bidirectional"))
      (node (ref "U$26") (pin "G") (pinfunction "G_G") (pintype "bidirectional"))
    )
    (net (code "39") (name "Net-(MAX7221-PadISET)") (class "Default")
      (node (ref "MAX7221") (pin "ISET") (pinfunction "ISET_ISET") (pintype "bidirectional"))
      (node (ref "R16") (pin "2") (pinfunction "2_2") (pintype "passive"))
    )
    (net (code "40") (name "Net-(PTC2-2)") (class "Default")
      (node (ref "PTC2") (pin "P$2") (pinfunction "2_P$2") (pintype "passive"))
      (node (ref "U$15") (pin "PWR2") (pinfunction "TIP_PWR2") (pintype "bidirectional"))
    )
    (net (code "41") (name "Net-(Q2-B)") (class "Default")
      (node (ref "Q2") (pin "1") (pinfunction "B_1") (pintype "passive"))
      (node (ref "R33") (pin "2") (pinfunction "2_2") (pintype "passive"))
      (node (ref "R34") (pin "2") (pinfunction "2_2") (pintype "passive"))
    )
    (net (code "42") (name "Net-(U$23-GN)") (class "Default")
      (node (ref "MAX7221") (pin "DIG0") (pinfunction "DIG0_DIG0") (pintype "bidirectional"))
      (node (ref "U$23") (pin "GND") (pinfunction "GN_GND") (pintype "bidirectional"))
      (node (ref "U$23") (pin "GND2") (pinfunction "GND_GND2") (pintype "bidirectional"))
    )
    (net (code "43") (name "Net-(U$24-GN)") (class "Default")
      (node (ref "MAX7221") (pin "DIG1") (pinfunction "DIG1_DIG1") (pintype "bidirectional"))
      (node (ref "U$24") (pin "GND") (pinfunction "GN_GND") (pintype "bidirectional"))
      (node (ref "U$24") (pin "GND2") (pinfunction "GND_GND2") (pintype "bidirectional"))
    )
    (net (code "44") (name "Net-(U$25-GN)") (class "Default")
      (node (ref "MAX7221") (pin "DIG2") (pinfunction "DIG2_DIG2") (pintype "bidirectional"))
      (node (ref "U$25") (pin "GND") (pinfunction "GN_GND") (pintype "bidirectional"))
      (node (ref "U$25") (pin "GND2") (pinfunction "GND_GND2") (pintype "bidirectional"))
    )
    (net (code "45") (name "Net-(U$26-GN)") (class "Default")
      (node (ref "MAX7221") (pin "DIG3") (pinfunction "DIG3_DIG3") (pintype "bidirectional"))
      (node (ref "U$26") (pin "GND") (pinfunction "GN_GND") (pintype "bidirectional"))
      (node (ref "U$26") (pin "GND2") (pinfunction "GND_GND2") (pintype "bidirectional"))
    )
    (net (code "46") (name "Net-(U2-B1)") (class "Default")
      (node (ref "MAX7221") (pin "DIN") (pinfunction "DIN_DIN") (pintype "bidirectional"))
      (node (ref "U2") (pin "20") (pinfunction "B1_20") (pintype "bidirectional"))
    )
    (net (code "47") (name "Net-(U2-B2)") (class "Default")
      (node (ref "MAX7221") (pin "CLK") (pinfunction "CLK_CLK") (pintype "bidirectional"))
      (node (ref "U2") (pin "18") (pinfunction "B2_18") (pintype "bidirectional"))
    )
    (net (code "48") (name "Net-(U2-B3)") (class "Default")
      (node (ref "MAX7221") (pin "LOAD") (pinfunction "LOAD_LOAD") (pintype "bidirectional"))
      (node (ref "U2") (pin "17") (pinfunction "B3_17") (pintype "bidirectional"))
    )
    (net (code "49") (name "Net-(U3-B1)") (class "Default")
      (node (ref "U$61") (pin "PIN1") (pinfunction "PIN1_PIN1") (pintype "bidirectional"))
      (node (ref "U3") (pin "20") (pinfunction "B1_20") (pintype "bidirectional"))
    )
    (net (code "50") (name "Net-(U3-B2)") (class "Default")
      (node (ref "U$61") (pin "PIN2") (pinfunction "PIN2_PIN2") (pintype "bidirectional"))
      (node (ref "U3") (pin "18") (pinfunction "B2_18") (pintype "bidirectional"))
    )
    (net (code "51") (name "Net-(U3-B3)") (class "Default")
      (node (ref "U$61") (pin "PIN3") (pinfunction "PIN3_PIN3") (pintype "bidirectional"))
      (node (ref "U3") (pin "17") (pinfunction "B3_17") (pintype "bidirectional"))
    )
    (net (code "52") (name "Net-(U3-B4)") (class "Default")
      (node (ref "U$61") (pin "PIN4") (pinfunction "PIN4_PIN4") (pintype "bidirectional"))
      (node (ref "U3") (pin "16") (pinfunction "B4_16") (pintype "bidirectional"))
    )
    (net (code "53") (name "Net-(U3-B5)") (class "Default")
      (node (ref "U$61") (pin "PIN5") (pinfunction "PIN5_PIN5") (pintype "bidirectional"))
      (node (ref "U3") (pin "15") (pinfunction "B5_15") (pintype "bidirectional"))
    )
    (net (code "54") (name "Net-(U3-B6)") (class "Default")
      (node (ref "U$61") (pin "PIN6") (pinfunction "PIN6_PIN6") (pintype "bidirectional"))
      (node (ref "U3") (pin "14") (pinfunction "B6_14") (pintype "bidirectional"))
    )
    (net (code "55") (name "Net-(XB1-ASSOC{slash}AD5{slash}DIO5)") (class "Default")
      (node (ref "LED9") (pin "A") (pinfunction "A_A") (pintype "passive"))
      (node (ref "XB1") (pin "15") (pinfunction "ASSOC/AD5/DIO5_15") (pintype "bidirectional"))
    )
    (net (code "56") (name "Net-(XB1-PWM0{slash}RSSI)") (class "Default")
      (node (ref "R17") (pin "1") (pinfunction "1_1") (pintype "passive"))
      (node (ref "XB1") (pin "6") (pinfunction "PWM0/RSSI_6") (pintype "output"))
    )
    (net (code "57") (name "PA0") (class "Default")
      (node (ref "U$1") (pin "P$75") (pinfunction "PA0_P$75") (pintype "bidirectional"))
    )
    (net (code "58") (name "PA1") (class "Default")
      (node (ref "U$1") (pin "P$76") (pinfunction "PA1_P$76") (pintype "bidirectional"))
    )
    (net (code "59") (name "PA2") (class "Default")
      (node (ref "U$1") (pin "P$77") (pinfunction "PA2_P$77") (pintype "bidirectional"))
    )
    (net (code "60") (name "PB4") (class "Default")
      (node (ref "U$1") (pin "P$54") (pinfunction "PB4_P$54") (pintype "bidirectional"))
    )
    (net (code "61") (name "PB9") (class "Default")
      (node (ref "U$1") (pin "P$59") (pinfunction "PB9_P$59") (pintype "bidirectional"))
    )
    (net (code "62") (name "PC0") (class "Default")
      (node (ref "U$1") (pin "P$71") (pinfunction "PC0_P$71") (pintype "bidirectional"))
    )
    (net (code "63") (name "PC1") (class "Default")
      (node (ref "U$1") (pin "P$72") (pinfunction "PC1_P$72") (pintype "bidirectional"))
    )
    (net (code "64") (name "PC2") (class "Default")
      (node (ref "U$1") (pin "P$73") (pinfunction "PC2_P$73") (pintype "bidirectional"))
    )
    (net (code "65") (name "PC3") (class "Default")
      (node (ref "U$1") (pin "P$74") (pinfunction "PC3_P$74") (pintype "bidirectional"))
    )
    (net (code "66") (name "PC13") (class "Default")
      (node (ref "U$1") (pin "P$68") (pinfunction "PC13_P$68") (pintype "bidirectional"))
    )
    (net (code "67") (name "PD4") (class "Default")
      (node (ref "U$1") (pin "P$50") (pinfunction "PD4_P$50") (pintype "bidirectional"))
    )
    (net (code "68") (name "PD7") (class "Default")
      (node (ref "U$1") (pin "P$53") (pinfunction "PD7_P$53") (pintype "bidirectional"))
    )
    (net (code "69") (name "PE0") (class "Default")
      (node (ref "U$1") (pin "P$60") (pinfunction "PE0_P$60") (pintype "bidirectional"))
    )
    (net (code "70") (name "PE1") (class "Default")
      (node (ref "U$1") (pin "P$61") (pinfunction "PE1_P$61") (pintype "bidirectional"))
    )
    (net (code "71") (name "PE2") (class "Default")
      (node (ref "U$1") (pin "P$63") (pinfunction "PE2_P$63") (pintype "bidirectional"))
    )
    (net (code "72") (name "PE3") (class "Default")
      (node (ref "U$1") (pin "P$64") (pinfunction "PE3_P$64") (pintype "bidirectional"))
    )
    (net (code "73") (name "PE4") (class "Default")
      (node (ref "U$1") (pin "P$65") (pinfunction "PE4_P$65") (pintype "bidirectional"))
    )
    (net (code "74") (name "PE5") (class "Default")
      (node (ref "U$1") (pin "P$66") (pinfunction "PE5_P$66") (pintype "bidirectional"))
    )
    (net (code "75") (name "PE6") (class "Default")
      (node (ref "U$1") (pin "P$67") (pinfunction "PE6_P$67") (pintype "bidirectional"))
    )
    (net (code "76") (name "RTS-XBEE") (class "Default")
      (node (ref "U$1") (pin "P$27") (pinfunction "PD8_P$27") (pintype "bidirectional"))
      (node (ref "XB1") (pin "16") (pinfunction "~{RTS}/AD6/DIO6_16") (pintype "bidirectional"))
    )
    (net (code "77") (name "SCL") (class "Default")
      (node (ref "U$1") (pin "P$58") (pinfunction "PB8_P$58") (pintype "bidirectional"))
    )
    (net (code "78") (name "SDA") (class "Default")
      (node (ref "U$1") (pin "P$57") (pinfunction "PB7_P$57") (pintype "bidirectional"))
    )
    (net (code "79") (name "SDIO_CK") (class "Default")
      (node (ref "U$1") (pin "P$47") (pinfunction "PC12_P$47") (pintype "bidirectional"))
      (node (ref "X3") (pin "5") (pinfunction "5_5") (pintype "passive"))
    )
    (net (code "80") (name "SDIO_CMD") (class "Default")
      (node (ref "R7") (pin "1") (pinfunction "1_1") (pintype "passive"))
      (node (ref "U$1") (pin "P$48") (pinfunction "PD2_P$48") (pintype "bidirectional"))
      (node (ref "X3") (pin "2") (pinfunction "2_2") (pintype "passive"))
    )
    (net (code "81") (name "SDIO_D0") (class "Default")
      (node (ref "R8") (pin "1") (pinfunction "1_1") (pintype "passive"))
      (node (ref "U$1") (pin "P$37") (pinfunction "PC8_P$37") (pintype "bidirectional"))
      (node (ref "X3") (pin "7") (pinfunction "7_7") (pintype "passive"))
    )
    (net (code "82") (name "SDIO_D1") (class "Default")
      (node (ref "R9") (pin "1") (pinfunction "1_1") (pintype "passive"))
      (node (ref "U$1") (pin "P$38") (pinfunction "PC9_P$38") (pintype "bidirectional"))
      (node (ref "X3") (pin "8") (pinfunction "8_8") (pintype "passive"))
    )
    (net (code "83") (name "SDIO_D2") (class "Default")
      (node (ref "R10") (pin "1") (pinfunction "1_1") (pintype "passive"))
      (node (ref "U$1") (pin "P$45") (pinfunction "PC10_P$45") (pintype "bidirectional"))
      (node (ref "X3") (pin "9") (pinfunction "9_9") (pintype "passive"))
    )
    (net (code "84") (name "SDIO_D3") (class "Default")
      (node (ref "R6") (pin "1") (pinfunction "1_1") (pintype "passive"))
      (node (ref "U$1") (pin "P$46") (pinfunction "PC11_P$46") (pintype "bidirectional"))
      (node (ref "X3") (pin "1") (pinfunction "1_1") (pintype "passive"))
    )
    (net (code "85") (name "SD_IN") (class "Default")
      (node (ref "U$1") (pin "P$49") (pinfunction "PD3_P$49") (pintype "bidirectional"))
      (node (ref "X3") (pin "SW1") (pinfunction "SW1_SW1") (pintype "passive"))
    )
    (net (code "86") (name "SPI_LOAD") (class "Default")
      (node (ref "U$1") (pin "P$40") (pinfunction "PA9_P$40") (pintype "bidirectional"))
      (node (ref "U2") (pin "4") (pinfunction "A3_4") (pintype "bidirectional"))
    )
    (net (code "87") (name "SPI_MISO") (class "Default")
      (node (ref "U$1") (pin "P$25") (pinfunction "PB14_P$25") (pintype "bidirectional"))
    )
    (net (code "88") (name "SPI_MOSI") (class "Default")
      (node (ref "U$1") (pin "P$26") (pinfunction "PB15_P$26") (pintype "bidirectional"))
      (node (ref "U2") (pin "1") (pinfunction "A1_1") (pintype "bidirectional"))
    )
    (net (code "89") (name "SPI_SCK") (class "Default")
      (node (ref "U$1") (pin "P$24") (pinfunction "PB13_P$24") (pintype "bidirectional"))
      (node (ref "U2") (pin "3") (pinfunction "A2_3") (pintype "bidirectional"))
    )
    (net (code "90") (name "SS-XBEE") (class "Default")
      (node (ref "C2") (pin "2") (pinfunction "P$2_2") (pintype "passive"))
      (node (ref "R17") (pin "2") (pinfunction "2_2") (pintype "passive"))
    )
    (net (code "91") (name "SW1") (class "Default")
      (node (ref "R2") (pin "1") (pinfunction "1_1") (pintype "passive"))
      (node (ref "S5") (pin "S") (pinfunction "S_S") (pintype "passive"))
      (node (ref "U$1") (pin "P$11") (pinfunction "PE8_P$11") (pintype "bidirectional"))
    )
    (net (code "92") (name "SW2") (class "Default")
      (node (ref "R3") (pin "1") (pinfunction "1_1") (pintype "passive"))
      (node (ref "S6") (pin "S") (pinfunction "S_S") (pintype "passive"))
      (node (ref "U$1") (pin "P$12") (pinfunction "PE9_P$12") (pintype "bidirectional"))
    )
    (net (code "93") (name "SW3") (class "Default")
      (node (ref "R4") (pin "1") (pinfunction "1_1") (pintype "passive"))
      (node (ref "S7") (pin "S") (pinfunction "S_S") (pintype "passive"))
      (node (ref "U$1") (pin "P$13") (pinfunction "PE10_P$13") (pintype "bidirectional"))
    )
    (net (code "94") (name "SW4") (class "Default")
      (node (ref "R5") (pin "1") (pinfunction "1_1") (pintype "passive"))
      (node (ref "S8") (pin "S") (pinfunction "S_S") (pintype "passive"))
      (node (ref "U$1") (pin "P$14") (pinfunction "PE11_P$14") (pintype "bidirectional"))
    )
    (net (code "95") (name "SW5") (class "Default")
      (node (ref "R11") (pin "1") (pinfunction "1_1") (pintype "passive"))
      (node (ref "S1") (pin "1") (pinfunction "S_1") (pintype "passive"))
      (node (ref "S1") (pin "2") (pinfunction "S1_2") (pintype "passive"))
      (node (ref "U$1") (pin "P$15") (pinfunction "PE12_P$15") (pintype "bidirectional"))
    )
    (net (code "96") (name "SW6") (class "Default")
      (node (ref "R12") (pin "1") (pinfunction "1_1") (pintype "passive"))
      (node (ref "S2") (pin "1") (pinfunction "S_1") (pintype "passive"))
      (node (ref "S2") (pin "2") (pinfunction "S1_2") (pintype "passive"))
      (node (ref "U$1") (pin "P$16") (pinfunction "PE13_P$16") (pintype "bidirectional"))
    )
    (net (code "97") (name "SW7") (class "Default")
      (node (ref "R13") (pin "1") (pinfunction "1_1") (pintype "passive"))
      (node (ref "S3") (pin "1") (pinfunction "S_1") (pintype "passive"))
      (node (ref "S3") (pin "2") (pinfunction "S1_2") (pintype "passive"))
      (node (ref "U$1") (pin "P$17") (pinfunction "PE14_P$17") (pintype "bidirectional"))
    )
    (net (code "98") (name "SW8") (class "Default")
      (node (ref "R14") (pin "1") (pinfunction "1_1") (pintype "passive"))
      (node (ref "S4") (pin "1") (pinfunction "S_1") (pintype "passive"))
      (node (ref "S4") (pin "2") (pinfunction "S1_2") (pintype "passive"))
      (node (ref "U$1") (pin "P$18") (pinfunction "PE15_P$18") (pintype "bidirectional"))
    )
    (net (code "99") (name "USART1_RX") (class "Default")
      (node (ref "U$1") (pin "P$22") (pinfunction "PB11_P$22") (pintype "bidirectional"))
      (node (ref "U$2") (pin "P$17") (pinfunction "TX_P$17") (pintype "bidirectional"))
      (node (ref "XB1") (pin "2") (pinfunction "DOUT_2") (pintype "output"))
    )
    (net (code "100") (name "USART1_TX") (class "Default")
      (node (ref "U$1") (pin "P$21") (pinfunction "PB10_P$21") (pintype "bidirectional"))
      (node (ref "U$2") (pin "P$18") (pinfunction "RX_P$18") (pintype "bidirectional"))
      (node (ref "XB1") (pin "3") (pinfunction "DIN/~{CONFIG}_3") (pintype "input"))
    )
    (net (code "101") (name "USART2_RX") (class "Default")
      (node (ref "U$1") (pin "P$52") (pinfunction "PD6_P$52") (pintype "bidirectional"))
    )
    (net (code "102") (name "USART2_TX") (class "Default")
      (node (ref "U$1") (pin "P$51") (pinfunction "PD5_P$51") (pintype "bidirectional"))
    )
    (net (code "103") (name "V-SENSE") (class "Default")
      (node (ref "Q2") (pin "2") (pinfunction "E_2") (pintype "passive"))
      (node (ref "U$1") (pin "P$39") (pinfunction "PA8_P$39") (pintype "bidirectional"))
    )
    (net (code "104") (name "unconnected-(MAX7221-PadDIG4)") (class "Default")
      (node (ref "MAX7221") (pin "DIG4") (pinfunction "DIG4_DIG4") (pintype "bidirectional"))
    )
    (net (code "105") (name "unconnected-(MAX7221-PadDIG5)") (class "Default")
      (node (ref "MAX7221") (pin "DIG5") (pinfunction "DIG5_DIG5") (pintype "bidirectional"))
    )
    (net (code "106") (name "unconnected-(MAX7221-PadDIG6)") (class "Default")
      (node (ref "MAX7221") (pin "DIG6") (pinfunction "DIG6_DIG6") (pintype "bidirectional"))
    )
    (net (code "107") (name "unconnected-(MAX7221-PadDIG7)") (class "Default")
      (node (ref "MAX7221") (pin "DIG7") (pinfunction "DIG7_DIG7") (pintype "bidirectional"))
    )
    (net (code "108") (name "unconnected-(MAX7221-PadDOUT)") (class "Default")
      (node (ref "MAX7221") (pin "DOUT") (pinfunction "DOUT_DOUT") (pintype "bidirectional"))
    )
    (net (code "109") (name "unconnected-(RV1-S-PadP$2)") (class "Default")
      (node (ref "RV1") (pin "P$2") (pinfunction "S_P$2") (pintype "passive"))
    )
    (net (code "110") (name "unconnected-(RV2-S-PadP$2)") (class "Default")
      (node (ref "RV2") (pin "P$2") (pinfunction "S_P$2") (pintype "passive"))
    )
    (net (code "111") (name "unconnected-(RV3-S-PadP$2)") (class "Default")
      (node (ref "RV3") (pin "P$2") (pinfunction "S_P$2") (pintype "passive"))
    )
    (net (code "112") (name "unconnected-(RV4-S-PadP$2)") (class "Default")
      (node (ref "RV4") (pin "P$2") (pinfunction "S_P$2") (pintype "passive"))
    )
    (net (code "113") (name "unconnected-(S5-PadO)") (class "Default")
      (node (ref "S5") (pin "O") (pinfunction "O_O") (pintype "passive"))
    )
    (net (code "114") (name "unconnected-(S6-PadO)") (class "Default")
      (node (ref "S6") (pin "O") (pinfunction "O_O") (pintype "passive"))
    )
    (net (code "115") (name "unconnected-(S7-PadO)") (class "Default")
      (node (ref "S7") (pin "O") (pinfunction "O_O") (pintype "passive"))
    )
    (net (code "116") (name "unconnected-(S8-PadO)") (class "Default")
      (node (ref "S8") (pin "O") (pinfunction "O_O") (pintype "passive"))
    )
    (net (code "117") (name "unconnected-(U$1A-PA3-PadP$1)") (class "Default")
      (node (ref "U$1") (pin "P$1") (pinfunction "PA3_P$1") (pintype "bidirectional"))
    )
    (net (code "118") (name "unconnected-(U$1A-PA4-PadP$2)") (class "Default")
      (node (ref "U$1") (pin "P$2") (pinfunction "PA4_P$2") (pintype "bidirectional"))
    )
    (net (code "119") (name "unconnected-(U$1B-PB12-PadP$23)") (class "Default")
      (node (ref "U$1") (pin "P$23") (pinfunction "PB12_P$23") (pintype "bidirectional"))
    )
    (net (code "120") (name "unconnected-(U$1B-PC6-PadP$35)") (class "Default")
      (node (ref "U$1") (pin "P$35") (pinfunction "PC6_P$35") (pintype "bidirectional"))
    )
    (net (code "121") (name "unconnected-(U$1B-PC7-PadP$36)") (class "Default")
      (node (ref "U$1") (pin "P$36") (pinfunction "PC7_P$36") (pintype "bidirectional"))
    )
    (net (code "122") (name "unconnected-(U$1B-PD10-PadP$29)") (class "Default")
      (node (ref "U$1") (pin "P$29") (pinfunction "PD10_P$29") (pintype "bidirectional"))
    )
    (net (code "123") (name "unconnected-(U$1B-PD11-PadP$30)") (class "Default")
      (node (ref "U$1") (pin "P$30") (pinfunction "PD11_P$30") (pintype "bidirectional"))
    )
    (net (code "124") (name "unconnected-(U$1B-PD12-PadP$31)") (class "Default")
      (node (ref "U$1") (pin "P$31") (pinfunction "PD12_P$31") (pintype "bidirectional"))
    )
    (net (code "125") (name "unconnected-(U$1B-PD13-PadP$32)") (class "Default")
      (node (ref "U$1") (pin "P$32") (pinfunction "PD13_P$32") (pintype "bidirectional"))
    )
    (net (code "126") (name "unconnected-(U$1B-PD14-PadP$33)") (class "Default")
      (node (ref "U$1") (pin "P$33") (pinfunction "PD14_P$33") (pintype "bidirectional"))
    )
    (net (code "127") (name "unconnected-(U$1B-PD15-PadP$34)") (class "Default")
      (node (ref "U$1") (pin "P$34") (pinfunction "PD15_P$34") (pintype "bidirectional"))
    )
    (net (code "128") (name "unconnected-(U$2-LRNLED-PadP$6)") (class "Default")
      (node (ref "U$2") (pin "P$6") (pinfunction "LRNLED_P$6") (pintype "bidirectional"))
    )
    (net (code "129") (name "unconnected-(U$2-LRNSW-PadP$5)") (class "Default")
      (node (ref "U$2") (pin "P$5") (pinfunction "LRNSW_P$5") (pintype "bidirectional"))
    )
    (net (code "130") (name "unconnected-(U$2-OP1-PadP$3)") (class "Default")
      (node (ref "U$2") (pin "P$3") (pinfunction "OP1_P$3") (pintype "bidirectional"))
    )
    (net (code "131") (name "unconnected-(U$2-OP2-PadP$4)") (class "Default")
      (node (ref "U$2") (pin "P$4") (pinfunction "OP2_P$4") (pintype "bidirectional"))
    )
    (net (code "132") (name "unconnected-(U$2-OP3-PadP$7)") (class "Default")
      (node (ref "U$2") (pin "P$7") (pinfunction "OP3_P$7") (pintype "bidirectional"))
    )
    (net (code "133") (name "unconnected-(U$2-OP4-PadP$8)") (class "Default")
      (node (ref "U$2") (pin "P$8") (pinfunction "OP4_P$8") (pintype "bidirectional"))
    )
    (net (code "134") (name "unconnected-(U$2-OP5-PadP$9)") (class "Default")
      (node (ref "U$2") (pin "P$9") (pinfunction "OP5_P$9") (pintype "bidirectional"))
    )
    (net (code "135") (name "unconnected-(U$2-OP6-PadP$11)") (class "Default")
      (node (ref "U$2") (pin "P$11") (pinfunction "OP6_P$11") (pintype "bidirectional"))
    )
    (net (code "136") (name "unconnected-(U$2-OP7-PadP$12)") (class "Default")
      (node (ref "U$2") (pin "P$12") (pinfunction "OP7_P$12") (pintype "bidirectional"))
    )
    (net (code "137") (name "unconnected-(U$2-OP8-PadP$13)") (class "Default")
      (node (ref "U$2") (pin "P$13") (pinfunction "OP8_P$13") (pintype "bidirectional"))
    )
    (net (code "138") (name "unconnected-(U$2-OPT1-PadP$10)") (class "Default")
      (node (ref "U$2") (pin "P$10") (pinfunction "OPT1_P$10") (pintype "bidirectional"))
    )
    (net (code "139") (name "unconnected-(U$61-PadPIN8)") (class "Default")
      (node (ref "U$61") (pin "PIN8") (pinfunction "PIN8_PIN8") (pintype "bidirectional"))
    )
    (net (code "140") (name "unconnected-(U$61-PadPIN9)") (class "Default")
      (node (ref "U$61") (pin "PIN9") (pinfunction "PIN9_PIN9") (pintype "bidirectional"))
    )
    (net (code "141") (name "unconnected-(U$61-PadPIN10)") (class "Default")
      (node (ref "U$61") (pin "PIN10") (pinfunction "PIN10_PIN10") (pintype "bidirectional"))
    )
    (net (code "142") (name "unconnected-(U$61-PadPIN11)") (class "Default")
      (node (ref "U$61") (pin "PIN11") (pinfunction "PIN11_PIN11") (pintype "bidirectional"))
    )
    (net (code "143") (name "unconnected-(U$61-PadPIN12)") (class "Default")
      (node (ref "U$61") (pin "PIN12") (pinfunction "PIN12_PIN12") (pintype "bidirectional"))
    )
    (net (code "144") (name "unconnected-(U$61-PadPIN13)") (class "Default")
      (node (ref "U$61") (pin "PIN13") (pinfunction "PIN13_PIN13") (pintype "bidirectional"))
    )
    (net (code "145") (name "unconnected-(U$61-PadPIN14)") (class "Default")
      (node (ref "U$61") (pin "PIN14") (pinfunction "PIN14_PIN14") (pintype "bidirectional"))
    )
    (net (code "146") (name "unconnected-(U$67-PadPIN1)") (class "Default")
      (node (ref "U$67") (pin "PIN1") (pinfunction "PIN1_PIN1") (pintype "bidirectional"))
    )
    (net (code "147") (name "unconnected-(U$67-PadPIN2)") (class "Default")
      (node (ref "U$67") (pin "PIN2") (pinfunction "PIN2_PIN2") (pintype "bidirectional"))
    )
    (net (code "148") (name "unconnected-(U$67-PadPIN3)") (class "Default")
      (node (ref "U$67") (pin "PIN3") (pinfunction "PIN3_PIN3") (pintype "bidirectional"))
    )
    (net (code "149") (name "unconnected-(U$67-PadPIN4)") (class "Default")
      (node (ref "U$67") (pin "PIN4") (pinfunction "PIN4_PIN4") (pintype "bidirectional"))
    )
    (net (code "150") (name "unconnected-(U$68-PadPIN1)") (class "Default")
      (node (ref "U$68") (pin "PIN1") (pinfunction "PIN1_PIN1") (pintype "bidirectional"))
    )
    (net (code "151") (name "unconnected-(U$68-PadPIN2)") (class "Default")
      (node (ref "U$68") (pin "PIN2") (pinfunction "PIN2_PIN2") (pintype "bidirectional"))
    )
    (net (code "152") (name "unconnected-(U$68-PadPIN3)") (class "Default")
      (node (ref "U$68") (pin "PIN3") (pinfunction "PIN3_PIN3") (pintype "bidirectional"))
    )
    (net (code "153") (name "unconnected-(U$68-PadPIN4)") (class "Default")
      (node (ref "U$68") (pin "PIN4") (pinfunction "PIN4_PIN4") (pintype "bidirectional"))
    )
    (net (code "154") (name "unconnected-(U$68-PadPIN5)") (class "Default")
      (node (ref "U$68") (pin "PIN5") (pinfunction "PIN5_PIN5") (pintype "bidirectional"))
    )
    (net (code "155") (name "unconnected-(U$68-PadPIN6)") (class "Default")
      (node (ref "U$68") (pin "PIN6") (pinfunction "PIN6_PIN6") (pintype "bidirectional"))
    )
    (net (code "156") (name "unconnected-(U2-A4-Pad5)") (class "Default")
      (node (ref "U2") (pin "5") (pinfunction "A4_5") (pintype "bidirectional"))
    )
    (net (code "157") (name "unconnected-(U2-A5-Pad6)") (class "Default")
      (node (ref "U2") (pin "6") (pinfunction "A5_6") (pintype "bidirectional"))
    )
    (net (code "158") (name "unconnected-(U2-A6-Pad7)") (class "Default")
      (node (ref "U2") (pin "7") (pinfunction "A6_7") (pintype "bidirectional"))
    )
    (net (code "159") (name "unconnected-(U2-A7-Pad8)") (class "Default")
      (node (ref "U2") (pin "8") (pinfunction "A7_8") (pintype "bidirectional"))
    )
    (net (code "160") (name "unconnected-(U2-A8-Pad9)") (class "Default")
      (node (ref "U2") (pin "9") (pinfunction "A8_9") (pintype "bidirectional"))
    )
    (net (code "161") (name "unconnected-(U2-B4-Pad16)") (class "Default")
      (node (ref "U2") (pin "16") (pinfunction "B4_16") (pintype "bidirectional"))
    )
    (net (code "162") (name "unconnected-(U2-B5-Pad15)") (class "Default")
      (node (ref "U2") (pin "15") (pinfunction "B5_15") (pintype "bidirectional"))
    )
    (net (code "163") (name "unconnected-(U2-B6-Pad14)") (class "Default")
      (node (ref "U2") (pin "14") (pinfunction "B6_14") (pintype "bidirectional"))
    )
    (net (code "164") (name "unconnected-(U2-B7-Pad13)") (class "Default")
      (node (ref "U2") (pin "13") (pinfunction "B7_13") (pintype "bidirectional"))
    )
    (net (code "165") (name "unconnected-(U2-B8-Pad12)") (class "Default")
      (node (ref "U2") (pin "12") (pinfunction "B8_12") (pintype "bidirectional"))
    )
    (net (code "166") (name "unconnected-(U3-A1-Pad1)") (class "Default")
      (node (ref "U3") (pin "1") (pinfunction "A1_1") (pintype "bidirectional"))
    )
    (net (code "167") (name "unconnected-(U3-A2-Pad3)") (class "Default")
      (node (ref "U3") (pin "3") (pinfunction "A2_3") (pintype "bidirectional"))
    )
    (net (code "168") (name "unconnected-(U3-A3-Pad4)") (class "Default")
      (node (ref "U3") (pin "4") (pinfunction "A3_4") (pintype "bidirectional"))
    )
    (net (code "169") (name "unconnected-(U3-A4-Pad5)") (class "Default")
      (node (ref "U3") (pin "5") (pinfunction "A4_5") (pintype "bidirectional"))
    )
    (net (code "170") (name "unconnected-(U3-A5-Pad6)") (class "Default")
      (node (ref "U3") (pin "6") (pinfunction "A5_6") (pintype "bidirectional"))
    )
    (net (code "171") (name "unconnected-(U3-A6-Pad7)") (class "Default")
      (node (ref "U3") (pin "7") (pinfunction "A6_7") (pintype "bidirectional"))
    )
    (net (code "172") (name "unconnected-(U3-A7-Pad8)") (class "Default")
      (node (ref "U3") (pin "8") (pinfunction "A7_8") (pintype "bidirectional"))
    )
    (net (code "173") (name "unconnected-(U3-A8-Pad9)") (class "Default")
      (node (ref "U3") (pin "9") (pinfunction "A8_9") (pintype "bidirectional"))
    )
    (net (code "174") (name "unconnected-(U3-B7-Pad13)") (class "Default")
      (node (ref "U3") (pin "13") (pinfunction "B7_13") (pintype "bidirectional"))
    )
    (net (code "175") (name "unconnected-(U3-B8-Pad12)") (class "Default")
      (node (ref "U3") (pin "12") (pinfunction "B8_12") (pintype "bidirectional"))
    )
    (net (code "176") (name "unconnected-(X3-PadSW2)") (class "Default")
      (node (ref "X3") (pin "SW2") (pinfunction "SW2_SW2") (pintype "passive"))
    )
    (net (code "177") (name "unconnected-(XB1-AD0{slash}DIO0-Pad20)") (class "Default")
      (node (ref "XB1") (pin "20") (pinfunction "AD0/DIO0_20") (pintype "bidirectional"))
    )
    (net (code "178") (name "unconnected-(XB1-AD1{slash}DIO1-Pad19)") (class "Default")
      (node (ref "XB1") (pin "19") (pinfunction "AD1/DIO1_19") (pintype "bidirectional"))
    )
    (net (code "179") (name "unconnected-(XB1-AD2{slash}DIO2-Pad18)") (class "Default")
      (node (ref "XB1") (pin "18") (pinfunction "AD2/DIO2_18") (pintype "bidirectional"))
    )
    (net (code "180") (name "unconnected-(XB1-CD{slash}DOUT_EN{slash}DO8-Pad4)") (class "Default")
      (node (ref "XB1") (pin "4") (pinfunction "CD/DOUT_EN/DO8_4") (pintype "output"))
    )
    (net (code "181") (name "unconnected-(XB1-COORD_SEL{slash}AD3{slash}DIO3-Pad17)") (class "Default")
      (node (ref "XB1") (pin "17") (pinfunction "COORD_SEL/AD3/DIO3_17") (pintype "bidirectional"))
    )
    (net (code "182") (name "unconnected-(XB1-ON{slash}~{SLEEP}-Pad13)") (class "Default")
      (node (ref "XB1") (pin "13") (pinfunction "ON/~{SLEEP}_13") (pintype "output"))
    )
    (net (code "183") (name "unconnected-(XB1-RF_TX{slash}AD4{slash}DIO4-Pad11)") (class "Default")
      (node (ref "XB1") (pin "11") (pinfunction "RF_TX/AD4/DIO4_11") (pintype "bidirectional"))
    )
    (net (code "184") (name "unconnected-(XB1-VREF-Pad14)") (class "Default")
      (node (ref "XB1") (pin "14") (pinfunction "VREF_14") (pintype "input"))
    )
    (net (code "185") (name "unconnected-(XB1-~{DTR}{slash}SLEEP_RQ{slash}DI8-Pad9)") (class "Default")
      (node (ref "XB1") (pin "9") (pinfunction "~{DTR}/SLEEP_RQ/DI8_9") (pintype "bidirectional"))
    )
  )
)
